# PreCharge.net
KiCad netlist of a schematic drawn in Altium Designer
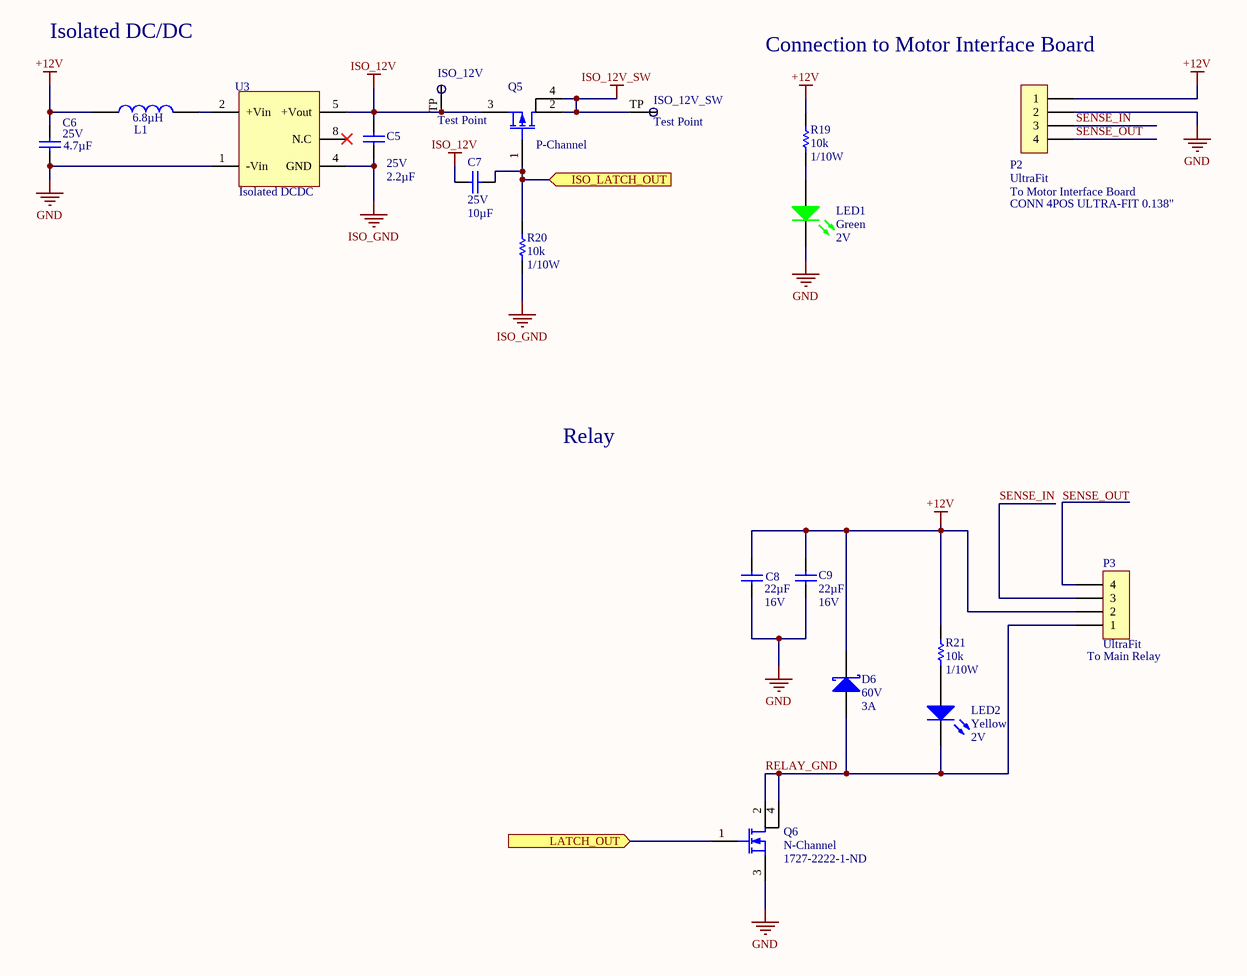
[diagram p0: PreCharge.SchDoc]

(export (version "E")
  (design (tool "Eeschema 10.0.6"))
  (components
    (comp (ref "C5")
      (value "CAP CER 2.2UF 25V 10% X5R 0603")
      (footprint "CAP, 0603")
      (description "2.2µF ±10% 25V Ceramic Capacitor X5R 0603 (1608 Metric)")
      (fields
        (field (name "VOLTAGE") "25V")
        (field (name "TOLERANCE") "±10%")
        (field (name "CAPACITANCE") "2.2µF")
      )
      (libsource (lib "Schematic Diagrams") (part "CAP CER 2.2UF 25V 10% X5R 0603"))
    )
    (comp (ref "C6")
      (value "CAP CER 4.7UF 25V 10% X5R 0603")
      (footprint "CAP, 0603")
      (description "4.7µF ±10% 25V Ceramic Capacitor X5R 0603 (1608 Metric)")
      (fields
        (field (name "VOLTAGE") "25V")
        (field (name "TOLERANCE") "±10%")
        (field (name "CAPACITANCE") "4.7µF")
      )
      (libsource (lib "Schematic Diagrams") (part "CAP CER 4.7UF 25V 10% X5R 0603"))
    )
    (comp (ref "C7")
      (value "CAP CER 10uF 25V 10% X5R 0805")
      (footprint "CAP, 0805")
      (description "10µF ±10% 25V Ceramic Capacitor X5R 0805 (2012 Metric)")
      (fields
        (field (name "MANUFACTURER") "Murata Electronics North America")
        (field (name "MANUFACTURER PART NUMBER") "GRM21BR61E106KA73L")
        (field (name "VOLTAGE - RATED") "25V")
        (field (name "CAPACITANCE") "10µF")
      )
      (libsource (lib "Schematic Diagrams") (part "CAP CER 10uF 25V 10% X5R 0805"))
    )
    (comp (ref "C8")
      (value "CAP CER 22UF 16V ±20% X5R 1210")
      (footprint "CAP, 1210")
      (description "22µF ±20% 16V Ceramic Capacitor X5R 1210 (3225 Metric)")
      (fields
        (field (name "TOLERANCE") "±20%")
        (field (name "CAPACITANCE") "22µF")
        (field (name "VOLTAGE") "16V")
      )
      (libsource (lib "Schematic Diagrams") (part "CAP CER 22UF 16V ±20% X5R 1210"))
    )
    (comp (ref "C9")
      (value "CAP CER 22UF 16V ±20% X5R 1210")
      (footprint "CAP, 1210")
      (description "22µF ±20% 16V Ceramic Capacitor X5R 1210 (3225 Metric)")
      (fields
        (field (name "TOLERANCE") "±20%")
        (field (name "CAPACITANCE") "22µF")
        (field (name "VOLTAGE") "16V")
      )
      (libsource (lib "Schematic Diagrams") (part "CAP CER 22UF 16V ±20% X5R 1210"))
    )
    (comp (ref "D6")
      (value "DIODE SCHOTTKY 60V 3A SMA")
      (footprint "SMA")
      (description "Diode Schottky 60V 3A Surface Mount SMA")
      (fields
        (field (name "VOLTAGE - DC REVERSE (VR) (MAX)") "60V")
        (field (name "CURRENT - AVERAGE RECTIFIED (IO)") "3A")
      )
      (libsource (lib "Schematic Diagrams") (part "DIODE SCHOTTKY 60V 3A SMA"))
    )
    (comp (ref "ISO_12V")
      (value "Test Point")
      (footprint "Test Point")
      (libsource (lib "Schematic Diagrams") (part "Test Point"))
    )
    (comp (ref "ISO_12V_SW")
      (value "Test Point")
      (footprint "Test Point")
      (libsource (lib "Schematic Diagrams") (part "Test Point"))
    )
    (comp (ref "L1")
      (value "IND 6.8uH 260mA 20% 1210")
      (footprint "NLFV32T-6R8M-EF/IND 6.8uH")
      (description "6.8µH Shielded Wirewound Inductor 260mA 204 mOhm Max 1210 (3225 Metric)")
      (fields (field (name "TOLERANCE") "±20%") (field (name "INDUCTANCE") "6.8µH"))
      (libsource (lib "Schematic Diagrams") (part "IND 6.8uH 260mA 20% 1210"))
    )
    (comp (ref "LED1")
      (value "LED GREEN CLEAR 2V 0603")
      (footprint "LED_0603")
      (description "Green 572nm LED Indication - Discrete 2V 0603 (1608 Metric)")
      (fields
        (field (name "MANUFACTURER") "Wurth Electronics Inc.")
        (field (name "MANUFACTURER PART NUMBER") "150060VS75000")
        (field (name "COLOR") "Green")
        (field (name "VOLTAGE - FORWARD (VF) (TYP)") "2V")
      )
      (libsource (lib "Schematic Diagrams") (part "LED GREEN CLEAR 2V 0603"))
    )
    (comp (ref "LED2")
      (value "LED YELLOW CLEAR 2.1V 0603")
      (footprint "LED_0603")
      (description "Yellow 590nm LED Indication - Discrete 2V 0603 (1608 Metric)")
      (fields
        (field (name "MANUFACTURER") "Wurth Electronics Inc.")
        (field (name "MANUFACTURER PART NUMBER") "150060YS75000")
        (field (name "COLOR") "Yellow")
        (field (name "VOLTAGE - FORWARD (VF) (TYP)") "2V")
      )
      (libsource (lib "Schematic Diagrams") (part "LED YELLOW CLEAR 2.1V 0603"))
    )
    (comp (ref "P2")
      (value "CONN 4POS ULTRA-FIT 0.138\"")
      (footprint "CONN, 4POS ULTRA-FIT")
      (description "4 Positions Header Connector 0.138\" (3.50mm) Through Hole Tin")
      (fields (field (name "VOLTAGE") "400V") (field (name "SERIES") "UltraFit"))
      (libsource (lib "") (part "CONN 4POS ULTRA-FIT 0.138{dblquote}_1"))
    )
    (comp (ref "P3")
      (value "CONN 4POS ULTRA-FIT 0.138\"")
      (footprint "CONN, 4POS ULTRA-FIT")
      (description "4 Positions Header Connector 0.138\" (3.50mm) Through Hole Tin")
      (fields (field (name "VOLTAGE") "400V") (field (name "SERIES") "UltraFit"))
      (libsource (lib "Schematic Diagrams") (part "CONN 4POS ULTRA-FIT 0.138{dblquote}"))
    )
    (comp (ref "Q5")
      (value "P-Channel")
      (footprint "SOT223_N")
      (description "P-Channel 60V 3A (Ta) 2W (Ta) Surface Mount SOT-223")
      (fields (field (name "MANUFACTURER") "Diodes") (field (name "MANUFACTURER PART NUMBER") "ZXMP6A17GQTA"))
      (libsource (lib "Schematic Diagrams") (part "MOSFET P-CH 60V 3A SOT223"))
    )
    (comp (ref "Q6")
      (value "N-Channel")
      (footprint "SOT223_N")
      (description "N-Channel 55V 7A (Tc) 8W (Tc) Surface Mount SOT-223")
      (fields
        (field (name "MANUFACTURER") "Nexperia")
        (field (name "MANUFACTURER PART NUMBER") "BUK7880-55A/CUX")
        (field (name "SUPPLIER PART NUMBER 1") "1727-2222-1-ND")
      )
      (libsource (lib "Schematic Diagrams") (part "MOSFET N-CH 55V 7A SOT223"))
    )
    (comp (ref "R19")
      (value "RES 10K OHM 1% 1/10W 0603")
      (footprint "RES, 0603")
      (description "RES SMD 10K OHM 1% 1/10W 0603")
      (fields
        (field (name "TOLERANCE") "±1%")
        (field (name "RESISTANCE") "10k")
        (field (name "POWER") "1/10W")
      )
      (libsource (lib "Schematic Diagrams") (part "RES 10K OHM 1% 1/10W 0603"))
    )
    (comp (ref "R20")
      (value "RES 10K OHM 1% 1/10W 0603")
      (footprint "RES, 0603")
      (description "RES SMD 10K OHM 1% 1/10W 0603")
      (fields
        (field (name "TOLERANCE") "±1%")
        (field (name "RESISTANCE") "10k")
        (field (name "POWER") "1/10W")
      )
      (libsource (lib "Schematic Diagrams") (part "RES 10K OHM 1% 1/10W 0603"))
    )
    (comp (ref "R21")
      (value "RES 10K OHM 1% 1/10W 0603")
      (footprint "RES, 0603")
      (description "RES SMD 10K OHM 1% 1/10W 0603")
      (fields
        (field (name "TOLERANCE") "±1%")
        (field (name "RESISTANCE") "10k")
        (field (name "POWER") "1/10W")
      )
      (libsource (lib "Schematic Diagrams") (part "RES 10K OHM 1% 1/10W 0603"))
    )
    (comp (ref "U3")
      (value "IC DCDC ISOLATED 12V 1W 8-SMD 5-LEAD")
      (footprint "IC, Isolated DCDC")
      (description "Isolated Module DC DC Converter 1 Output 12V 84mA 10.8V - 13.2V Input")
      (fields (field (name "POWER") "1W") (field (name "TYPE") "Isolated DCDC"))
      (libsource (lib "Schematic Diagrams") (part "IC DCDC ISOLATED 12V 1W 8-SMD 5-LEAD"))
    )
  )
  (nets
    (net (code "1") (name "+12V") (class "Default")
      (node (ref "C6") (pin "2") (pinfunction "2_2") (pintype "passive"))
      (node (ref "C8") (pin "1") (pinfunction "1_1") (pintype "passive"))
      (node (ref "C9") (pin "1") (pinfunction "1_1") (pintype "passive"))
      (node (ref "D6") (pin "2") (pinfunction "2_2") (pintype "passive"))
      (node (ref "L1") (pin "1") (pinfunction "1_1") (pintype "passive"))
      (node (ref "P2") (pin "1") (pinfunction "1_1") (pintype "passive"))
      (node (ref "P3") (pin "2") (pinfunction "2_2") (pintype "passive"))
      (node (ref "R19") (pin "2") (pinfunction "2_2") (pintype "passive"))
      (node (ref "R21") (pin "1") (pinfunction "1_1") (pintype "passive"))
    )
    (net (code "2") (name "/ISO_LATCH_OUT") (class "Default")
      (node (ref "C7") (pin "2") (pinfunction "2_2") (pintype "passive"))
      (node (ref "Q5") (pin "1") (pinfunction "G_1") (pintype "passive"))
      (node (ref "R20") (pin "1") (pinfunction "1_1") (pintype "passive"))
    )
    (net (code "3") (name "/LATCH_OUT") (class "Default")
      (node (ref "Q6") (pin "1") (pinfunction "G_1") (pintype "passive"))
    )
    (net (code "4") (name "/RELAY_GND") (class "Default")
      (node (ref "D6") (pin "1") (pinfunction "1_1") (pintype "passive"))
      (node (ref "LED2") (pin "2") (pinfunction "K_2") (pintype "passive"))
      (node (ref "P3") (pin "1") (pinfunction "1_1") (pintype "passive"))
      (node (ref "Q6") (pin "2") (pinfunction "D_2") (pintype "passive"))
      (node (ref "Q6") (pin "4") (pinfunction "D_4") (pintype "passive"))
    )
    (net (code "5") (name "/SENSE_IN") (class "Default")
      (node (ref "P2") (pin "3") (pinfunction "3_3") (pintype "passive"))
      (node (ref "P3") (pin "3") (pinfunction "3_3") (pintype "passive"))
    )
    (net (code "6") (name "/SENSE_OUT") (class "Default")
      (node (ref "P2") (pin "4") (pinfunction "4_4") (pintype "passive"))
      (node (ref "P3") (pin "4") (pinfunction "4_4") (pintype "passive"))
    )
    (net (code "7") (name "GND") (class "Default")
      (node (ref "C6") (pin "1") (pinfunction "1_1") (pintype "passive"))
      (node (ref "C8") (pin "2") (pinfunction "2_2") (pintype "passive"))
      (node (ref "C9") (pin "2") (pinfunction "2_2") (pintype "passive"))
      (node (ref "LED1") (pin "2") (pinfunction "K_2") (pintype "passive"))
      (node (ref "P2") (pin "2") (pinfunction "2_2") (pintype "passive"))
      (node (ref "Q6") (pin "3") (pinfunction "S_3") (pintype "passive"))
      (node (ref "U3") (pin "1") (pinfunction "-Vin_1") (pintype "passive"))
    )
    (net (code "8") (name "ISO_12V") (class "Default")
      (node (ref "C5") (pin "2") (pinfunction "2_2") (pintype "passive"))
      (node (ref "C7") (pin "1") (pinfunction "1_1") (pintype "passive"))
      (node (ref "ISO_12V") (pin "TP") (pinfunction "1_TP") (pintype "passive"))
      (node (ref "Q5") (pin "3") (pinfunction "S_3") (pintype "passive"))
      (node (ref "U3") (pin "5") (pinfunction "+Vout_5") (pintype "passive"))
    )
    (net (code "9") (name "ISO_12V_SW") (class "Default")
      (node (ref "ISO_12V_SW") (pin "TP") (pinfunction "1_TP") (pintype "passive"))
      (node (ref "Q5") (pin "2") (pinfunction "D_2") (pintype "passive"))
      (node (ref "Q5") (pin "4") (pinfunction "D_4") (pintype "passive"))
    )
    (net (code "10") (name "ISO_GND") (class "Default")
      (node (ref "C5") (pin "1") (pinfunction "1_1") (pintype "passive"))
      (node (ref "R20") (pin "2") (pinfunction "2_2") (pintype "passive"))
      (node (ref "U3") (pin "4") (pinfunction "GND_4") (pintype "passive"))
    )
    (net (code "11") (name "Net-(LED1-A)") (class "Default")
      (node (ref "LED1") (pin "1") (pinfunction "A_1") (pintype "passive"))
      (node (ref "R19") (pin "1") (pinfunction "1_1") (pintype "passive"))
    )
    (net (code "12") (name "Net-(LED2-A)") (class "Default")
      (node (ref "LED2") (pin "1") (pinfunction "A_1") (pintype "passive"))
      (node (ref "R21") (pin "2") (pinfunction "2_2") (pintype "passive"))
    )
    (net (code "13") (name "Net-(U3-+Vin)") (class "Default")
      (node (ref "L1") (pin "2") (pinfunction "2_2") (pintype "passive"))
      (node (ref "U3") (pin "2") (pinfunction "+Vin_2") (pintype "passive"))
    )
    (net (code "14") (name "unconnected-(U3-N.C-Pad8)") (class "Default")
      (node (ref "U3") (pin "8") (pinfunction "N.C_8") (pintype "passive+no_connect"))
    )
  )
)
